# Driver_Controls_Board_v1_4.net
KiCad netlist of a schematic drawn in EAGLE
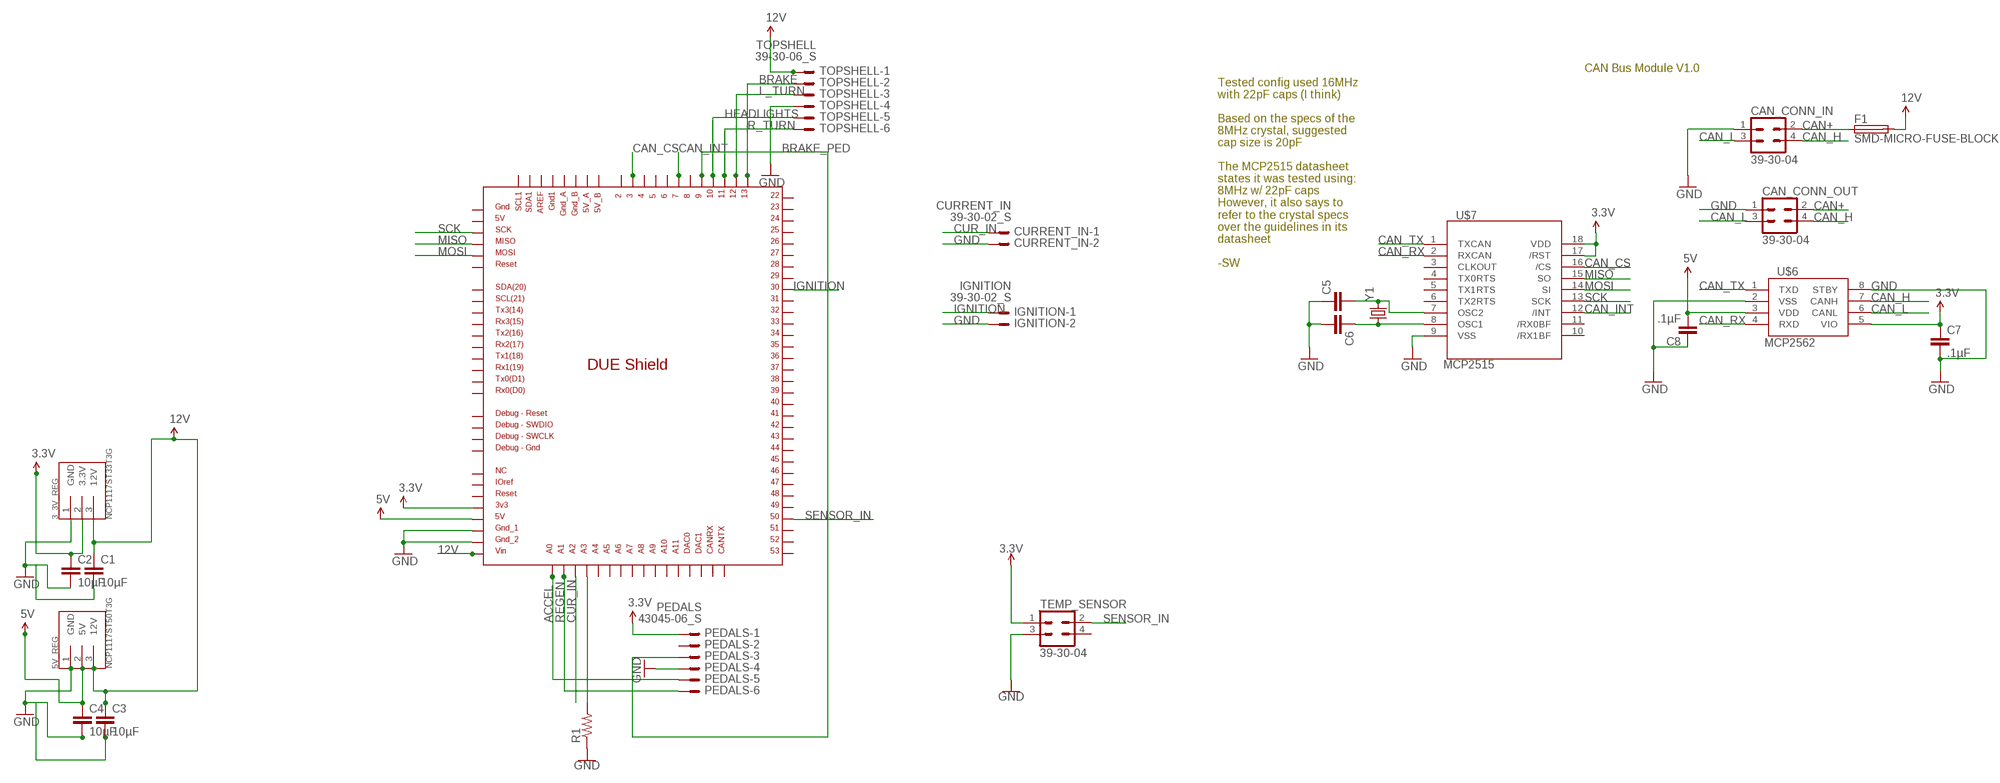
[diagram p0: schematic, sheet 1]

(export (version "E")
  (design (tool "Eeschema 10.0.6"))
  (components
    (comp (ref "3_3V_REG")
      (value "NCP1117ST33T3G")
      (footprint "eagle-import:SOT223")
      (libsource (lib "eagle-import") (part "NCP1117ST33T3G"))
    )
    (comp (ref "5V_REG")
      (value "NCP1117ST50T3G")
      (footprint "eagle-import:SOT223")
      (libsource (lib "eagle-import") (part "NCP1117ST50T3G"))
    )
    (comp (ref "C1")
      (value "10µF")
      (footprint "eagle-import:0805")
      (libsource (lib "eagle-import") (part "CAP0805"))
    )
    (comp (ref "C2")
      (value "10µF")
      (footprint "eagle-import:0805")
      (libsource (lib "eagle-import") (part "CAP0805"))
    )
    (comp (ref "C3")
      (value "10µF")
      (footprint "eagle-import:0805")
      (libsource (lib "eagle-import") (part "CAP0805"))
    )
    (comp (ref "C4")
      (value "10µF")
      (footprint "eagle-import:0805")
      (libsource (lib "eagle-import") (part "CAP0805"))
    )
    (comp (ref "C5")
      (value "CAP0805")
      (footprint "eagle-import:0805")
      (libsource (lib "eagle-import") (part "CAP0805"))
    )
    (comp (ref "C6")
      (value "CAP0805")
      (footprint "eagle-import:0805")
      (libsource (lib "eagle-import") (part "CAP0805"))
    )
    (comp (ref "C7")
      (value ".1µF")
      (footprint "eagle-import:0805")
      (libsource (lib "eagle-import") (part "CAP0805"))
    )
    (comp (ref "C8")
      (value ".1µF")
      (footprint "eagle-import:0805")
      (libsource (lib "eagle-import") (part "CAP0805"))
    )
    (comp (ref "CAN_CONN_IN")
      (value "39-30-04")
      (footprint "eagle-import:39-30-_04_")
      (libsource (lib "eagle-import") (part "39-30-?04?"))
    )
    (comp (ref "CAN_CONN_OUT")
      (value "39-30-04")
      (footprint "eagle-import:39-30-_04_")
      (libsource (lib "eagle-import") (part "39-30-?04?"))
    )
    (comp (ref "CURRENT_IN")
      (value "39-30-02_S")
      (footprint "eagle-import:39-30-_02_")
      (libsource (lib "eagle-import") (part "39-30-?02?_S"))
    )
    (comp (ref "F1")
      (value "SMD-MICRO-FUSE-BLOCK")
      (footprint "eagle-import:OMNIBLOK")
      (libsource (lib "eagle-import") (part "SMD-MICRO-FUSE-BLOCK"))
    )
    (comp (ref "IGNITION")
      (value "39-30-02_S")
      (footprint "eagle-import:39-30-_02_")
      (libsource (lib "eagle-import") (part "39-30-?02?_S"))
    )
    (comp (ref "PEDALS")
      (value "43045-06_S")
      (footprint "eagle-import:43045-06")
      (libsource (lib "eagle-import") (part "43045-06_S"))
    )
    (comp (ref "R1")
      (value "R-US_0204/5")
      (footprint "eagle-import:0204_5")
      (libsource (lib "eagle-import") (part "R-US_0204/5"))
    )
    (comp (ref "TEMP_SENSOR")
      (value "39-30-04")
      (footprint "eagle-import:39-30-_04_")
      (libsource (lib "eagle-import") (part "39-30-?04?"))
    )
    (comp (ref "TOPSHELL")
      (value "39-30-06_S")
      (footprint "eagle-import:39-30-_06_")
      (libsource (lib "eagle-import") (part "39-30-?06?_S"))
    )
    (comp (ref "U$2")
      (value "DUE(NORMAL)")
      (footprint "eagle-import:DUE(NORMAL)")
      (libsource (lib "eagle-import") (part "DUE(NORMAL)"))
    )
    (comp (ref "U$6")
      (value "MCP2562")
      (footprint "eagle-import:SOIC8")
      (libsource (lib "eagle-import") (part "MCP2562"))
    )
    (comp (ref "U$7")
      (value "MCP2515")
      (footprint "eagle-import:SO-18W")
      (libsource (lib "eagle-import") (part "MCP2515"))
    )
    (comp (ref "Y1")
      (value "CRYSTALHC49US")
      (footprint "eagle-import:HC49US")
      (libsource (lib "eagle-import") (part "CRYSTALHC49US"))
    )
  )
  (nets
    (net (code "1") (name "/ACCEL") (class "Default")
      (node (ref "PEDALS") (pin "5") (pinfunction "P_5") (pintype "passive"))
      (node (ref "U$2") (pin "A0") (pinfunction "A0_A0") (pintype "bidirectional"))
    )
    (net (code "2") (name "/BRAKE") (class "Default")
      (node (ref "TOPSHELL") (pin "2") (pinfunction "P_2") (pintype "passive"))
      (node (ref "U$2") (pin "13") (pinfunction "13_13") (pintype "bidirectional"))
    )
    (net (code "3") (name "/BRAKE_PED") (class "Default")
      (node (ref "PEDALS") (pin "3") (pinfunction "P_3") (pintype "passive"))
      (node (ref "U$2") (pin "9") (pinfunction "9_9") (pintype "bidirectional"))
    )
    (net (code "4") (name "/CAN+") (class "Default")
      (node (ref "CAN_CONN_IN") (pin "2") (pinfunction "2_2") (pintype "passive"))
      (node (ref "CAN_CONN_OUT") (pin "2") (pinfunction "2_2") (pintype "passive"))
      (node (ref "F1") (pin "P$1") (pinfunction "1_P$1") (pintype "passive"))
    )
    (net (code "5") (name "/CAN_CS") (class "Default")
      (node (ref "U$2") (pin "3") (pinfunction "3_3") (pintype "bidirectional"))
      (node (ref "U$7") (pin "16") (pinfunction "/CS_16") (pintype "bidirectional"))
    )
    (net (code "6") (name "/CAN_H") (class "Default")
      (node (ref "CAN_CONN_IN") (pin "4") (pinfunction "4_4") (pintype "passive"))
      (node (ref "CAN_CONN_OUT") (pin "4") (pinfunction "4_4") (pintype "passive"))
      (node (ref "U$6") (pin "7") (pinfunction "CANH_7") (pintype "bidirectional"))
    )
    (net (code "7") (name "/CAN_INT") (class "Default")
      (node (ref "U$2") (pin "7") (pinfunction "7_7") (pintype "bidirectional"))
      (node (ref "U$7") (pin "12") (pinfunction "/INT_12") (pintype "bidirectional"))
    )
    (net (code "8") (name "/CAN_L") (class "Default")
      (node (ref "CAN_CONN_IN") (pin "3") (pinfunction "3_3") (pintype "passive"))
      (node (ref "CAN_CONN_OUT") (pin "3") (pinfunction "3_3") (pintype "passive"))
      (node (ref "U$6") (pin "6") (pinfunction "CANL_6") (pintype "bidirectional"))
    )
    (net (code "9") (name "/CAN_RX") (class "Default")
      (node (ref "U$6") (pin "4") (pinfunction "RXD_4") (pintype "bidirectional"))
      (node (ref "U$7") (pin "2") (pinfunction "RXCAN_2") (pintype "bidirectional"))
    )
    (net (code "10") (name "/CAN_TX") (class "Default")
      (node (ref "U$6") (pin "1") (pinfunction "TXD_1") (pintype "bidirectional"))
      (node (ref "U$7") (pin "1") (pinfunction "TXCAN_1") (pintype "bidirectional"))
    )
    (net (code "11") (name "/CUR_IN") (class "Default")
      (node (ref "CURRENT_IN") (pin "1") (pinfunction "P_1") (pintype "passive"))
      (node (ref "U$2") (pin "A2") (pinfunction "A2_A2") (pintype "bidirectional"))
    )
    (net (code "12") (name "/HEADLIGHTS") (class "Default")
      (node (ref "TOPSHELL") (pin "5") (pinfunction "P_5") (pintype "passive"))
      (node (ref "U$2") (pin "10") (pinfunction "10_10") (pintype "bidirectional"))
    )
    (net (code "13") (name "/IGNITION") (class "Default")
      (node (ref "IGNITION") (pin "1") (pinfunction "P_1") (pintype "passive"))
      (node (ref "U$2") (pin "30") (pinfunction "30_30") (pintype "bidirectional"))
    )
    (net (code "14") (name "/L_TURN") (class "Default")
      (node (ref "TOPSHELL") (pin "3") (pinfunction "P_3") (pintype "passive"))
      (node (ref "U$2") (pin "12") (pinfunction "12_12") (pintype "bidirectional"))
    )
    (net (code "15") (name "/MISO") (class "Default")
      (node (ref "U$2") (pin "MISO_ICSP") (pinfunction "MISO_ICSP_MISO_ICSP") (pintype "bidirectional"))
      (node (ref "U$7") (pin "15") (pinfunction "SO_15") (pintype "bidirectional"))
    )
    (net (code "16") (name "/MOSI") (class "Default")
      (node (ref "U$2") (pin "MOSI_ICSP") (pinfunction "MOSI_ICSP_MOSI_ICSP") (pintype "bidirectional"))
      (node (ref "U$7") (pin "14") (pinfunction "SI_14") (pintype "bidirectional"))
    )
    (net (code "17") (name "/REGEN") (class "Default")
      (node (ref "PEDALS") (pin "6") (pinfunction "P_6") (pintype "passive"))
      (node (ref "U$2") (pin "A1") (pinfunction "A1_A1") (pintype "bidirectional"))
    )
    (net (code "18") (name "/R_TURN") (class "Default")
      (node (ref "TOPSHELL") (pin "6") (pinfunction "P_6") (pintype "passive"))
      (node (ref "U$2") (pin "11") (pinfunction "11_11") (pintype "bidirectional"))
    )
    (net (code "19") (name "/SCK") (class "Default")
      (node (ref "U$2") (pin "SCK_ICSP") (pinfunction "SCK_ICSP_SCK_ICSP") (pintype "bidirectional"))
      (node (ref "U$7") (pin "13") (pinfunction "SCK_13") (pintype "bidirectional"))
    )
    (net (code "20") (name "/SENSOR_IN") (class "Default")
      (node (ref "TEMP_SENSOR") (pin "2") (pinfunction "2_2") (pintype "passive"))
      (node (ref "U$2") (pin "50") (pinfunction "50_50") (pintype "bidirectional"))
    )
    (net (code "21") (name "3.3V") (class "Default")
      (node (ref "3_3V_REG") (pin "2") (pinfunction "3.3V_2") (pintype "bidirectional"))
      (node (ref "C2") (pin "1") (pinfunction "1_1") (pintype "passive"))
      (node (ref "C7") (pin "1") (pinfunction "1_1") (pintype "passive"))
      (node (ref "PEDALS") (pin "1") (pinfunction "P_1") (pintype "passive"))
      (node (ref "TEMP_SENSOR") (pin "1") (pinfunction "1_1") (pintype "passive"))
      (node (ref "U$2") (pin "3V3") (pinfunction "3V3_3V3") (pintype "bidirectional"))
      (node (ref "U$6") (pin "5") (pinfunction "VIO_5") (pintype "bidirectional"))
      (node (ref "U$7") (pin "17") (pinfunction "/RST_17") (pintype "bidirectional"))
      (node (ref "U$7") (pin "18") (pinfunction "VDD_18") (pintype "bidirectional"))
    )
    (net (code "22") (name "5V") (class "Default")
      (node (ref "5V_REG") (pin "2") (pinfunction "5V_2") (pintype "bidirectional"))
      (node (ref "C4") (pin "1") (pinfunction "1_1") (pintype "passive"))
      (node (ref "C8") (pin "2") (pinfunction "2_2") (pintype "passive"))
      (node (ref "U$2") (pin "5V") (pinfunction "5V_5V") (pintype "bidirectional"))
      (node (ref "U$6") (pin "3") (pinfunction "VDD_3") (pintype "bidirectional"))
    )
    (net (code "23") (name "12V") (class "Default")
      (node (ref "3_3V_REG") (pin "3") (pinfunction "12V_3") (pintype "bidirectional"))
      (node (ref "5V_REG") (pin "3") (pinfunction "12V_3") (pintype "bidirectional"))
      (node (ref "C1") (pin "1") (pinfunction "1_1") (pintype "passive"))
      (node (ref "C3") (pin "1") (pinfunction "1_1") (pintype "passive"))
      (node (ref "F1") (pin "P$2") (pinfunction "2_P$2") (pintype "passive"))
      (node (ref "TOPSHELL") (pin "1") (pinfunction "P_1") (pintype "passive"))
      (node (ref "U$2") (pin "VIN") (pinfunction "VIN_VIN") (pintype "bidirectional"))
    )
    (net (code "24") (name "GND") (class "Default")
      (node (ref "3_3V_REG") (pin "1") (pinfunction "GND_1") (pintype "bidirectional"))
      (node (ref "5V_REG") (pin "1") (pinfunction "GND_1") (pintype "bidirectional"))
      (node (ref "C1") (pin "2") (pinfunction "2_2") (pintype "passive"))
      (node (ref "C2") (pin "2") (pinfunction "2_2") (pintype "passive"))
      (node (ref "C3") (pin "2") (pinfunction "2_2") (pintype "passive"))
      (node (ref "C4") (pin "2") (pinfunction "2_2") (pintype "passive"))
      (node (ref "C5") (pin "1") (pinfunction "1_1") (pintype "passive"))
      (node (ref "C6") (pin "2") (pinfunction "2_2") (pintype "passive"))
      (node (ref "C7") (pin "2") (pinfunction "2_2") (pintype "passive"))
      (node (ref "C8") (pin "1") (pinfunction "1_1") (pintype "passive"))
      (node (ref "CAN_CONN_IN") (pin "1") (pinfunction "1_1") (pintype "passive"))
      (node (ref "CAN_CONN_OUT") (pin "1") (pinfunction "1_1") (pintype "passive"))
      (node (ref "CURRENT_IN") (pin "2") (pinfunction "P_2") (pintype "passive"))
      (node (ref "IGNITION") (pin "2") (pinfunction "P_2") (pintype "passive"))
      (node (ref "PEDALS") (pin "4") (pinfunction "P_4") (pintype "passive"))
      (node (ref "R1") (pin "1") (pinfunction "1_1") (pintype "passive"))
      (node (ref "TEMP_SENSOR") (pin "3") (pinfunction "3_3") (pintype "passive"))
      (node (ref "TOPSHELL") (pin "4") (pinfunction "P_4") (pintype "passive"))
      (node (ref "U$2") (pin "GND_1") (pinfunction "GND_1_GND_1") (pintype "bidirectional"))
      (node (ref "U$2") (pin "GND_2") (pinfunction "GND_2_GND_2") (pintype "bidirectional"))
      (node (ref "U$6") (pin "2") (pinfunction "VSS_2") (pintype "bidirectional"))
      (node (ref "U$6") (pin "8") (pinfunction "STBY_8") (pintype "bidirectional"))
      (node (ref "U$7") (pin "9") (pinfunction "VSS_9") (pintype "bidirectional"))
    )
    (net (code "25") (name "Net-(R1-Pad2)") (class "Default")
      (node (ref "R1") (pin "2") (pinfunction "2_2") (pintype "passive"))
      (node (ref "U$2") (pin "A3") (pinfunction "A3_A3") (pintype "bidirectional"))
    )
    (net (code "26") (name "Net-(U$7-OSC1)") (class "Default")
      (node (ref "C6") (pin "1") (pinfunction "1_1") (pintype "passive"))
      (node (ref "U$7") (pin "8") (pinfunction "OSC1_8") (pintype "bidirectional"))
      (node (ref "Y1") (pin "1") (pinfunction "1_1") (pintype "passive"))
    )
    (net (code "27") (name "Net-(U$7-OSC2)") (class "Default")
      (node (ref "C5") (pin "2") (pinfunction "2_2") (pintype "passive"))
      (node (ref "U$7") (pin "7") (pinfunction "OSC2_7") (pintype "bidirectional"))
      (node (ref "Y1") (pin "2") (pinfunction "2_2") (pintype "passive"))
    )
    (net (code "28") (name "unconnected-(PEDALSB-P-Pad2)") (class "Default")
      (node (ref "PEDALS") (pin "2") (pinfunction "P_2") (pintype "passive"))
    )
    (net (code "29") (name "unconnected-(TEMP_SENSOR-Pad4)") (class "Default")
      (node (ref "TEMP_SENSOR") (pin "4") (pinfunction "4_4") (pintype "passive"))
    )
    (net (code "30") (name "unconnected-(U$2-Pad2)") (class "Default")
      (node (ref "U$2") (pin "2") (pinfunction "2_2") (pintype "bidirectional"))
    )
    (net (code "31") (name "unconnected-(U$2-Pad4)") (class "Default")
      (node (ref "U$2") (pin "4") (pinfunction "4_4") (pintype "bidirectional"))
    )
    (net (code "32") (name "unconnected-(U$2-Pad5)") (class "Default")
      (node (ref "U$2") (pin "5") (pinfunction "5_5") (pintype "bidirectional"))
    )
    (net (code "33") (name "unconnected-(U$2-Pad5V_A)") (class "Default")
      (node (ref "U$2") (pin "5V_A") (pinfunction "5V_A_5V_A") (pintype "bidirectional"))
    )
    (net (code "34") (name "unconnected-(U$2-Pad5V_B)") (class "Default")
      (node (ref "U$2") (pin "5V_B") (pinfunction "5V_B_5V_B") (pintype "bidirectional"))
    )
    (net (code "35") (name "unconnected-(U$2-Pad5V_ICSP)") (class "Default")
      (node (ref "U$2") (pin "5V_ICSP") (pinfunction "5V_ICSP_5V_ICSP") (pintype "bidirectional"))
    )
    (net (code "36") (name "unconnected-(U$2-Pad6)") (class "Default")
      (node (ref "U$2") (pin "6") (pinfunction "6_6") (pintype "bidirectional"))
    )
    (net (code "37") (name "unconnected-(U$2-Pad8)") (class "Default")
      (node (ref "U$2") (pin "8") (pinfunction "8_8") (pintype "bidirectional"))
    )
    (net (code "38") (name "unconnected-(U$2-Pad22)") (class "Default")
      (node (ref "U$2") (pin "22") (pinfunction "22_22") (pintype "bidirectional"))
    )
    (net (code "39") (name "unconnected-(U$2-Pad23)") (class "Default")
      (node (ref "U$2") (pin "23") (pinfunction "23_23") (pintype "bidirectional"))
    )
    (net (code "40") (name "unconnected-(U$2-Pad24)") (class "Default")
      (node (ref "U$2") (pin "24") (pinfunction "24_24") (pintype "bidirectional"))
    )
    (net (code "41") (name "unconnected-(U$2-Pad25)") (class "Default")
      (node (ref "U$2") (pin "25") (pinfunction "25_25") (pintype "bidirectional"))
    )
    (net (code "42") (name "unconnected-(U$2-Pad26)") (class "Default")
      (node (ref "U$2") (pin "26") (pinfunction "26_26") (pintype "bidirectional"))
    )
    (net (code "43") (name "unconnected-(U$2-Pad27)") (class "Default")
      (node (ref "U$2") (pin "27") (pinfunction "27_27") (pintype "bidirectional"))
    )
    (net (code "44") (name "unconnected-(U$2-Pad28)") (class "Default")
      (node (ref "U$2") (pin "28") (pinfunction "28_28") (pintype "bidirectional"))
    )
    (net (code "45") (name "unconnected-(U$2-Pad29)") (class "Default")
      (node (ref "U$2") (pin "29") (pinfunction "29_29") (pintype "bidirectional"))
    )
    (net (code "46") (name "unconnected-(U$2-Pad31)") (class "Default")
      (node (ref "U$2") (pin "31") (pinfunction "31_31") (pintype "bidirectional"))
    )
    (net (code "47") (name "unconnected-(U$2-Pad32)") (class "Default")
      (node (ref "U$2") (pin "32") (pinfunction "32_32") (pintype "bidirectional"))
    )
    (net (code "48") (name "unconnected-(U$2-Pad33)") (class "Default")
      (node (ref "U$2") (pin "33") (pinfunction "33_33") (pintype "bidirectional"))
    )
    (net (code "49") (name "unconnected-(U$2-Pad34)") (class "Default")
      (node (ref "U$2") (pin "34") (pinfunction "34_34") (pintype "bidirectional"))
    )
    (net (code "50") (name "unconnected-(U$2-Pad35)") (class "Default")
      (node (ref "U$2") (pin "35") (pinfunction "35_35") (pintype "bidirectional"))
    )
    (net (code "51") (name "unconnected-(U$2-Pad36)") (class "Default")
      (node (ref "U$2") (pin "36") (pinfunction "36_36") (pintype "bidirectional"))
    )
    (net (code "52") (name "unconnected-(U$2-Pad37)") (class "Default")
      (node (ref "U$2") (pin "37") (pinfunction "37_37") (pintype "bidirectional"))
    )
    (net (code "53") (name "unconnected-(U$2-Pad38)") (class "Default")
      (node (ref "U$2") (pin "38") (pinfunction "38_38") (pintype "bidirectional"))
    )
    (net (code "54") (name "unconnected-(U$2-Pad39)") (class "Default")
      (node (ref "U$2") (pin "39") (pinfunction "39_39") (pintype "bidirectional"))
    )
    (net (code "55") (name "unconnected-(U$2-Pad40)") (class "Default")
      (node (ref "U$2") (pin "40") (pinfunction "40_40") (pintype "bidirectional"))
    )
    (net (code "56") (name "unconnected-(U$2-Pad41)") (class "Default")
      (node (ref "U$2") (pin "41") (pinfunction "41_41") (pintype "bidirectional"))
    )
    (net (code "57") (name "unconnected-(U$2-Pad42)") (class "Default")
      (node (ref "U$2") (pin "42") (pinfunction "42_42") (pintype "bidirectional"))
    )
    (net (code "58") (name "unconnected-(U$2-Pad43)") (class "Default")
      (node (ref "U$2") (pin "43") (pinfunction "43_43") (pintype "bidirectional"))
    )
    (net (code "59") (name "unconnected-(U$2-Pad44)") (class "Default")
      (node (ref "U$2") (pin "44") (pinfunction "44_44") (pintype "bidirectional"))
    )
    (net (code "60") (name "unconnected-(U$2-Pad45)") (class "Default")
      (node (ref "U$2") (pin "45") (pinfunction "45_45") (pintype "bidirectional"))
    )
    (net (code "61") (name "unconnected-(U$2-Pad46)") (class "Default")
      (node (ref "U$2") (pin "46") (pinfunction "46_46") (pintype "bidirectional"))
    )
    (net (code "62") (name "unconnected-(U$2-Pad47)") (class "Default")
      (node (ref "U$2") (pin "47") (pinfunction "47_47") (pintype "bidirectional"))
    )
    (net (code "63") (name "unconnected-(U$2-Pad48)") (class "Default")
      (node (ref "U$2") (pin "48") (pinfunction "48_48") (pintype "bidirectional"))
    )
    (net (code "64") (name "unconnected-(U$2-Pad49)") (class "Default")
      (node (ref "U$2") (pin "49") (pinfunction "49_49") (pintype "bidirectional"))
    )
    (net (code "65") (name "unconnected-(U$2-Pad51)") (class "Default")
      (node (ref "U$2") (pin "51") (pinfunction "51_51") (pintype "bidirectional"))
    )
    (net (code "66") (name "unconnected-(U$2-Pad52)") (class "Default")
      (node (ref "U$2") (pin "52") (pinfunction "52_52") (pintype "bidirectional"))
    )
    (net (code "67") (name "unconnected-(U$2-Pad53)") (class "Default")
      (node (ref "U$2") (pin "53") (pinfunction "53_53") (pintype "bidirectional"))
    )
    (net (code "68") (name "unconnected-(U$2-PadA4)") (class "Default")
      (node (ref "U$2") (pin "A4") (pinfunction "A4_A4") (pintype "bidirectional"))
    )
    (net (code "69") (name "unconnected-(U$2-PadA5)") (class "Default")
      (node (ref "U$2") (pin "A5") (pinfunction "A5_A5") (pintype "bidirectional"))
    )
    (net (code "70") (name "unconnected-(U$2-PadA6)") (class "Default")
      (node (ref "U$2") (pin "A6") (pinfunction "A6_A6") (pintype "bidirectional"))
    )
    (net (code "71") (name "unconnected-(U$2-PadA7)") (class "Default")
      (node (ref "U$2") (pin "A7") (pinfunction "A7_A7") (pintype "bidirectional"))
    )
    (net (code "72") (name "unconnected-(U$2-PadA8)") (class "Default")
      (node (ref "U$2") (pin "A8") (pinfunction "A8_A8") (pintype "bidirectional"))
    )
    (net (code "73") (name "unconnected-(U$2-PadA9)") (class "Default")
      (node (ref "U$2") (pin "A9") (pinfunction "A9_A9") (pintype "bidirectional"))
    )
    (net (code "74") (name "unconnected-(U$2-PadA10)") (class "Default")
      (node (ref "U$2") (pin "A10") (pinfunction "A10_A10") (pintype "bidirectional"))
    )
    (net (code "75") (name "unconnected-(U$2-PadA11)") (class "Default")
      (node (ref "U$2") (pin "A11") (pinfunction "A11_A11") (pintype "bidirectional"))
    )
    (net (code "76") (name "unconnected-(U$2-PadAREF)") (class "Default")
      (node (ref "U$2") (pin "AREF") (pinfunction "AREF_AREF") (pintype "bidirectional"))
    )
    (net (code "77") (name "unconnected-(U$2-PadCANRX)") (class "Default")
      (node (ref "U$2") (pin "CANRX") (pinfunction "CANRX_CANRX") (pintype "bidirectional"))
    )
    (net (code "78") (name "unconnected-(U$2-PadCANTX)") (class "Default")
      (node (ref "U$2") (pin "CANTX") (pinfunction "CANTX_CANTX") (pintype "bidirectional"))
    )
    (net (code "79") (name "unconnected-(U$2-PadDAC0)") (class "Default")
      (node (ref "U$2") (pin "DAC0") (pinfunction "DAC0_DAC0") (pintype "bidirectional"))
    )
    (net (code "80") (name "unconnected-(U$2-PadDAC1)") (class "Default")
      (node (ref "U$2") (pin "DAC1") (pinfunction "DAC1_DAC1") (pintype "bidirectional"))
    )
    (net (code "81") (name "unconnected-(U$2-PadGND1)") (class "Default")
      (node (ref "U$2") (pin "GND1") (pinfunction "GND1_GND1") (pintype "bidirectional"))
    )
    (net (code "82") (name "unconnected-(U$2-PadGND_A)") (class "Default")
      (node (ref "U$2") (pin "GND_A") (pinfunction "GND_A_GND_A") (pintype "bidirectional"))
    )
    (net (code "83") (name "unconnected-(U$2-PadGND_B)") (class "Default")
      (node (ref "U$2") (pin "GND_B") (pinfunction "GND_B_GND_B") (pintype "bidirectional"))
    )
    (net (code "84") (name "unconnected-(U$2-PadGND_DEBUG)") (class "Default")
      (node (ref "U$2") (pin "GND_DEBUG") (pinfunction "GND_DEBUG_GND_DEBUG") (pintype "bidirectional"))
    )
    (net (code "85") (name "unconnected-(U$2-PadGND_ICSP)") (class "Default")
      (node (ref "U$2") (pin "GND_ICSP") (pinfunction "GND_ICSP_GND_ICSP") (pintype "bidirectional"))
    )
    (net (code "86") (name "unconnected-(U$2-PadIOREF)") (class "Default")
      (node (ref "U$2") (pin "IOREF") (pinfunction "IOREF_IOREF") (pintype "bidirectional"))
    )
    (net (code "87") (name "unconnected-(U$2-PadNC)") (class "Default")
      (node (ref "U$2") (pin "NC") (pinfunction "NC_NC") (pintype "bidirectional"))
    )
    (net (code "88") (name "unconnected-(U$2-PadRESET)") (class "Default")
      (node (ref "U$2") (pin "RESET") (pinfunction "RESET_RESET") (pintype "bidirectional"))
    )
    (net (code "89") (name "unconnected-(U$2-PadRESET_DEBUG)") (class "Default")
      (node (ref "U$2") (pin "RESET_DEBUG") (pinfunction "RESET_DEBUG_RESET_DEBUG") (pintype "bidirectional"))
    )
    (net (code "90") (name "unconnected-(U$2-PadRESET_ICSP)") (class "Default")
      (node (ref "U$2") (pin "RESET_ICSP") (pinfunction "RESET_ICSP_RESET_ICSP") (pintype "bidirectional"))
    )
    (net (code "91") (name "unconnected-(U$2-PadRX0)") (class "Default")
      (node (ref "U$2") (pin "RX0") (pinfunction "RX0_RX0") (pintype "bidirectional"))
    )
    (net (code "92") (name "unconnected-(U$2-PadRX1)") (class "Default")
      (node (ref "U$2") (pin "RX1") (pinfunction "RX1_RX1") (pintype "bidirectional"))
    )
    (net (code "93") (name "unconnected-(U$2-PadRX2)") (class "Default")
      (node (ref "U$2") (pin "RX2") (pinfunction "RX2_RX2") (pintype "bidirectional"))
    )
    (net (code "94") (name "unconnected-(U$2-PadRX3)") (class "Default")
      (node (ref "U$2") (pin "RX3") (pinfunction "RX3_RX3") (pintype "bidirectional"))
    )
    (net (code "95") (name "unconnected-(U$2-PadSCL)") (class "Default")
      (node (ref "U$2") (pin "SCL") (pinfunction "SCL_SCL") (pintype "bidirectional"))
    )
    (net (code "96") (name "unconnected-(U$2-PadSCL1)") (class "Default")
      (node (ref "U$2") (pin "SCL1") (pinfunction "SCL1_SCL1") (pintype "bidirectional"))
    )
    (net (code "97") (name "unconnected-(U$2-PadSDA)") (class "Default")
      (node (ref "U$2") (pin "SDA") (pinfunction "SDA_SDA") (pintype "bidirectional"))
    )
    (net (code "98") (name "unconnected-(U$2-PadSDA1)") (class "Default")
      (node (ref "U$2") (pin "SDA1") (pinfunction "SDA1_SDA1") (pintype "bidirectional"))
    )
    (net (code "99") (name "unconnected-(U$2-PadSWCLK_DEBUG)") (class "Default")
      (node (ref "U$2") (pin "SWCLK_DEBUG") (pinfunction "SWCLK_DEBUG_SWCLK_DEBUG") (pintype "bidirectional"))
    )
    (net (code "100") (name "unconnected-(U$2-PadSWDIO_DEBUG)") (class "Default")
      (node (ref "U$2") (pin "SWDIO_DEBUG") (pinfunction "SWDIO_DEBUG_SWDIO_DEBUG") (pintype "bidirectional"))
    )
    (net (code "101") (name "unconnected-(U$2-PadTX0)") (class "Default")
      (node (ref "U$2") (pin "TX0") (pinfunction "TX0_TX0") (pintype "bidirectional"))
    )
    (net (code "102") (name "unconnected-(U$2-PadTX1)") (class "Default")
      (node (ref "U$2") (pin "TX1") (pinfunction "TX1_TX1") (pintype "bidirectional"))
    )
    (net (code "103") (name "unconnected-(U$2-PadTX2)") (class "Default")
      (node (ref "U$2") (pin "TX2") (pinfunction "TX2_TX2") (pintype "bidirectional"))
    )
    (net (code "104") (name "unconnected-(U$2-PadTX3)") (class "Default")
      (node (ref "U$2") (pin "TX3") (pinfunction "TX3_TX3") (pintype "bidirectional"))
    )
    (net (code "105") (name "unconnected-(U$7-CLKOUT-Pad3)") (class "Default")
      (node (ref "U$7") (pin "3") (pinfunction "CLKOUT_3") (pintype "bidirectional"))
    )
    (net (code "106") (name "unconnected-(U$7-TX0RTS-Pad4)") (class "Default")
      (node (ref "U$7") (pin "4") (pinfunction "TX0RTS_4") (pintype "bidirectional"))
    )
    (net (code "107") (name "unconnected-(U$7-TX1RTS-Pad5)") (class "Default")
      (node (ref "U$7") (pin "5") (pinfunction "TX1RTS_5") (pintype "bidirectional"))
    )
    (net (code "108") (name "unconnected-(U$7-TX2RTS-Pad6)") (class "Default")
      (node (ref "U$7") (pin "6") (pinfunction "TX2RTS_6") (pintype "bidirectional"))
    )
    (net (code "109") (name "unconnected-(U$7-{slash}RX0BF-Pad11)") (class "Default")
      (node (ref "U$7") (pin "11") (pinfunction "/RX0BF_11") (pintype "bidirectional"))
    )
    (net (code "110") (name "unconnected-(U$7-{slash}RX1BF-Pad10)") (class "Default")
      (node (ref "U$7") (pin "10") (pinfunction "/RX1BF_10") (pintype "bidirectional"))
    )
  )
)
